# internal_env_board.net
KiCad netlist of a schematic drawn in EAGLE
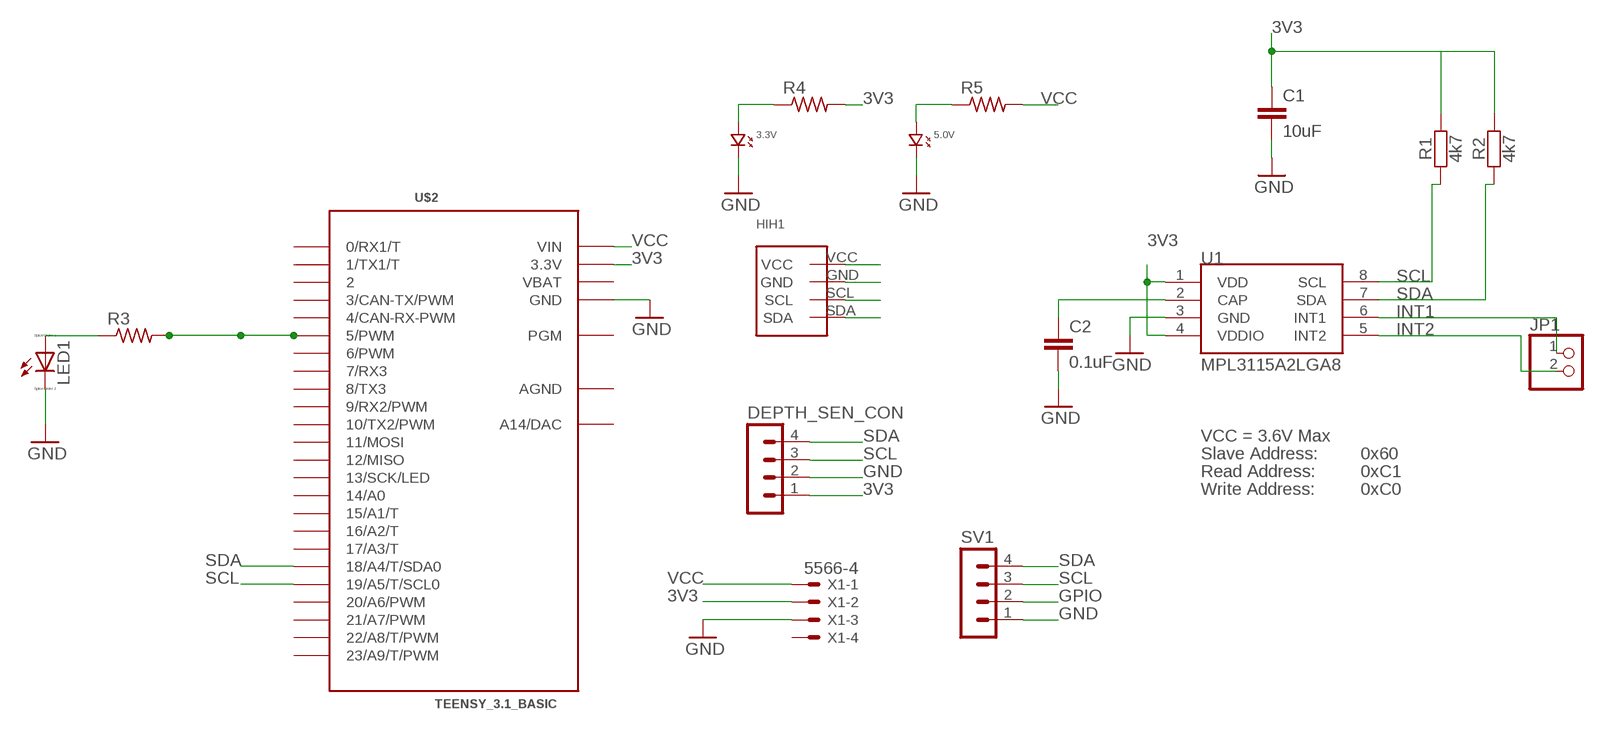
[diagram p0: schematic, sheet 1]

(export (version "E")
  (design (tool "Eeschema 10.0.6"))
  (components
    (comp (ref "3.3V")
      (value "LED.0805")
      (footprint "eagle-import:0805.LED")
      (libsource (lib "eagle-import") (part "LED.0805"))
    )
    (comp (ref "5.0V")
      (value "LED.0805")
      (footprint "eagle-import:0805.LED")
      (libsource (lib "eagle-import") (part "LED.0805"))
    )
    (comp (ref "C1")
      (value "10uF")
      (footprint "eagle-import:0805")
      (libsource (lib "eagle-import") (part "CAP0805"))
    )
    (comp (ref "C2")
      (value "0.1uF")
      (footprint "eagle-import:0805")
      (libsource (lib "eagle-import") (part "CAP0805"))
    )
    (comp (ref "DEPTH_SEN_CON")
      (value "MA04-1")
      (footprint "eagle-import:MA04-1")
      (libsource (lib "eagle-import") (part "MA04-1"))
    )
    (comp (ref "HIH1")
      (value "HIH7120")
      (footprint "eagle-import:SIP4")
      (libsource (lib "eagle-import") (part "HIH7120"))
    )
    (comp (ref "JP1")
      (value "PINHD-1X2")
      (footprint "eagle-import:1X02")
      (libsource (lib "eagle-import") (part "PINHD-1X2"))
    )
    (comp (ref "LED1")
      (value "LED_E")
      (footprint "eagle-import:LED_1206")
      (libsource (lib "eagle-import") (part "LED_E"))
    )
    (comp (ref "R1")
      (value "4k7")
      (footprint "eagle-import:R0805")
      (libsource (lib "eagle-import") (part "RESISTOR-R0805"))
    )
    (comp (ref "R2")
      (value "4k7")
      (footprint "eagle-import:R0805")
      (libsource (lib "eagle-import") (part "RESISTOR-R0805"))
    )
    (comp (ref "R3")
      (value "R-US_M1206")
      (footprint "eagle-import:M1206")
      (libsource (lib "eagle-import") (part "resistor_R-US_M1206"))
    )
    (comp (ref "R4")
      (value "R-US_R0805")
      (footprint "eagle-import:R0805")
      (libsource (lib "eagle-import") (part "R-US_R0805"))
    )
    (comp (ref "R5")
      (value "R-US_R0805")
      (footprint "eagle-import:R0805")
      (libsource (lib "eagle-import") (part "R-US_R0805"))
    )
    (comp (ref "SV1")
      (value "MA04-1")
      (footprint "eagle-import:MA04-1")
      (libsource (lib "eagle-import") (part "MA04-1"))
    )
    (comp (ref "U$2")
      (value "TEENSY_3.1_BASIC")
      (footprint "eagle-import:TEENSY_3.1_BASIC")
      (libsource (lib "eagle-import") (part "TEENSY_3.1_BASIC"))
    )
    (comp (ref "U1")
      (value "MPL3115A2LGA8")
      (footprint "eagle-import:LGA8")
      (libsource (lib "eagle-import") (part "MPL3115A2LGA8"))
    )
    (comp (ref "X1")
      (value "5566-4")
      (footprint "eagle-import:5566-4")
      (libsource (lib "eagle-import") (part "5566-4"))
    )
  )
  (nets
    (net (code "1") (name "/3V3") (class "Default")
      (node (ref "C1") (pin "1") (pinfunction "1_1") (pintype "passive"))
      (node (ref "DEPTH_SEN_CON") (pin "1") (pinfunction "1_1") (pintype "passive"))
      (node (ref "HIH1") (pin "VCC") (pinfunction "VCC_VCC") (pintype "power_in"))
      (node (ref "R1") (pin "2") (pinfunction "2_2") (pintype "passive"))
      (node (ref "R2") (pin "2") (pinfunction "2_2") (pintype "passive"))
      (node (ref "R4") (pin "2") (pinfunction "2_2") (pintype "passive"))
      (node (ref "U$2") (pin "3.3V") (pinfunction "3.3V_3.3V") (pintype "power_in"))
      (node (ref "U$2") (pin "3.3V1") (pinfunction "3.3V_3.3V1") (pintype "power_in"))
      (node (ref "U1") (pin "1") (pinfunction "VDD_1") (pintype "bidirectional"))
      (node (ref "U1") (pin "4") (pinfunction "VDDIO_4") (pintype "bidirectional"))
      (node (ref "X1") (pin "2") (pinfunction "S_2") (pintype "passive"))
    )
    (net (code "2") (name "/AGND") (class "Default")
      (node (ref "U$2") (pin "AGND") (pinfunction "AGND_AGND") (pintype "power_in"))
    )
    (net (code "3") (name "/GPIO") (class "Default")
      (node (ref "R3") (pin "2") (pinfunction "2_2") (pintype "passive"))
      (node (ref "SV1") (pin "2") (pinfunction "2_2") (pintype "passive"))
      (node (ref "U$2") (pin "5") (pinfunction "5/PWM_5") (pintype "bidirectional"))
    )
    (net (code "4") (name "/INT1") (class "Default")
      (node (ref "JP1") (pin "1") (pinfunction "1_1") (pintype "passive"))
      (node (ref "U1") (pin "6") (pinfunction "INT1_6") (pintype "bidirectional"))
    )
    (net (code "5") (name "/INT2") (class "Default")
      (node (ref "JP1") (pin "2") (pinfunction "2_2") (pintype "passive"))
      (node (ref "U1") (pin "5") (pinfunction "INT2_5") (pintype "bidirectional"))
    )
    (net (code "6") (name "/SCL") (class "Default")
      (node (ref "DEPTH_SEN_CON") (pin "3") (pinfunction "3_3") (pintype "passive"))
      (node (ref "HIH1") (pin "SCL") (pinfunction "SCL_SCL") (pintype "bidirectional"))
      (node (ref "R1") (pin "1") (pinfunction "1_1") (pintype "passive"))
      (node (ref "SV1") (pin "3") (pinfunction "3_3") (pintype "passive"))
      (node (ref "U$2") (pin "19/A5") (pinfunction "19/A5/T/SCL0_19/A5") (pintype "bidirectional"))
      (node (ref "U1") (pin "8") (pinfunction "SCL_8") (pintype "bidirectional"))
    )
    (net (code "7") (name "/SDA") (class "Default")
      (node (ref "DEPTH_SEN_CON") (pin "4") (pinfunction "4_4") (pintype "passive"))
      (node (ref "HIH1") (pin "SDA") (pinfunction "SDA_SDA") (pintype "bidirectional"))
      (node (ref "R2") (pin "1") (pinfunction "1_1") (pintype "passive"))
      (node (ref "SV1") (pin "4") (pinfunction "4_4") (pintype "passive"))
      (node (ref "U$2") (pin "18/A4") (pinfunction "18/A4/T/SDA0_18/A4") (pintype "bidirectional"))
      (node (ref "U1") (pin "7") (pinfunction "SDA_7") (pintype "bidirectional"))
    )
    (net (code "8") (name "/VBAT") (class "Default")
      (node (ref "U$2") (pin "VBAT") (pinfunction "VBAT_VBAT") (pintype "power_in"))
    )
    (net (code "9") (name "/VCC") (class "Default")
      (node (ref "R5") (pin "2") (pinfunction "2_2") (pintype "passive"))
      (node (ref "U$2") (pin "VIN") (pinfunction "VIN_VIN") (pintype "power_in"))
      (node (ref "X1") (pin "1") (pinfunction "S_1") (pintype "passive"))
    )
    (net (code "10") (name "GND") (class "Default")
      (node (ref "3.3V") (pin "P$2") (pinfunction "2_P$2") (pintype "bidirectional"))
      (node (ref "5.0V") (pin "P$2") (pinfunction "2_P$2") (pintype "bidirectional"))
      (node (ref "C1") (pin "2") (pinfunction "2_2") (pintype "passive"))
      (node (ref "C2") (pin "2") (pinfunction "2_2") (pintype "passive"))
      (node (ref "DEPTH_SEN_CON") (pin "2") (pinfunction "2_2") (pintype "passive"))
      (node (ref "HIH1") (pin "GND") (pinfunction "GND_GND") (pintype "power_in"))
      (node (ref "LED1") (pin "C") (pinfunction "C_C") (pintype "passive"))
      (node (ref "SV1") (pin "1") (pinfunction "1_1") (pintype "passive"))
      (node (ref "U$2") (pin "GND") (pinfunction "GND_GND") (pintype "power_in"))
      (node (ref "U$2") (pin "GND1") (pinfunction "GND_GND1") (pintype "power_in"))
      (node (ref "U1") (pin "3") (pinfunction "GND_3") (pintype "bidirectional"))
      (node (ref "X1") (pin "3") (pinfunction "S_3") (pintype "passive"))
    )
    (net (code "11") (name "Net-(3.3V-1)") (class "Default")
      (node (ref "3.3V") (pin "P$1") (pinfunction "1_P$1") (pintype "bidirectional"))
      (node (ref "R4") (pin "1") (pinfunction "1_1") (pintype "passive"))
    )
    (net (code "12") (name "Net-(5.0V-1)") (class "Default")
      (node (ref "5.0V") (pin "P$1") (pinfunction "1_P$1") (pintype "bidirectional"))
      (node (ref "R5") (pin "1") (pinfunction "1_1") (pintype "passive"))
    )
    (net (code "13") (name "Net-(LED1-PadA)") (class "Default")
      (node (ref "LED1") (pin "A") (pinfunction "A_A") (pintype "passive"))
      (node (ref "R3") (pin "1") (pinfunction "1_1") (pintype "passive"))
    )
    (net (code "14") (name "Net-(U1-CAP)") (class "Default")
      (node (ref "C2") (pin "1") (pinfunction "1_1") (pintype "passive"))
      (node (ref "U1") (pin "2") (pinfunction "CAP_2") (pintype "bidirectional"))
    )
    (net (code "15") (name "unconnected-(U$2-0{slash}RX1{slash}T-Pad0)") (class "Default")
      (node (ref "U$2") (pin "0") (pinfunction "0/RX1/T_0") (pintype "bidirectional"))
    )
    (net (code "16") (name "unconnected-(U$2-1{slash}TX1{slash}T-Pad1)") (class "Default")
      (node (ref "U$2") (pin "1") (pinfunction "1/TX1/T_1") (pintype "bidirectional"))
    )
    (net (code "17") (name "unconnected-(U$2-3{slash}CAN-TX{slash}PWM-Pad3)") (class "Default")
      (node (ref "U$2") (pin "3") (pinfunction "3/CAN-TX/PWM_3") (pintype "bidirectional"))
    )
    (net (code "18") (name "unconnected-(U$2-4{slash}CAN-RX-PWM-Pad4)") (class "Default")
      (node (ref "U$2") (pin "4") (pinfunction "4/CAN-RX-PWM_4") (pintype "bidirectional"))
    )
    (net (code "19") (name "unconnected-(U$2-6{slash}PWM-Pad6)") (class "Default")
      (node (ref "U$2") (pin "6") (pinfunction "6/PWM_6") (pintype "bidirectional"))
    )
    (net (code "20") (name "unconnected-(U$2-7{slash}RX3-Pad7)") (class "Default")
      (node (ref "U$2") (pin "7") (pinfunction "7/RX3_7") (pintype "bidirectional"))
    )
    (net (code "21") (name "unconnected-(U$2-8{slash}TX3-Pad8)") (class "Default")
      (node (ref "U$2") (pin "8") (pinfunction "8/TX3_8") (pintype "bidirectional"))
    )
    (net (code "22") (name "unconnected-(U$2-9{slash}RX2{slash}PWM-Pad9)") (class "Default")
      (node (ref "U$2") (pin "9") (pinfunction "9/RX2/PWM_9") (pintype "bidirectional"))
    )
    (net (code "23") (name "unconnected-(U$2-10{slash}TX2{slash}PWM-Pad10)") (class "Default")
      (node (ref "U$2") (pin "10") (pinfunction "10/TX2/PWM_10") (pintype "bidirectional"))
    )
    (net (code "24") (name "unconnected-(U$2-11{slash}MOSI-Pad11)") (class "Default")
      (node (ref "U$2") (pin "11") (pinfunction "11/MOSI_11") (pintype "bidirectional"))
    )
    (net (code "25") (name "unconnected-(U$2-12{slash}MISO-Pad12)") (class "Default")
      (node (ref "U$2") (pin "12") (pinfunction "12/MISO_12") (pintype "bidirectional"))
    )
    (net (code "26") (name "unconnected-(U$2-13{slash}SCK{slash}LED-Pad13)") (class "Default")
      (node (ref "U$2") (pin "13") (pinfunction "13/SCK/LED_13") (pintype "bidirectional"))
    )
    (net (code "27") (name "unconnected-(U$2-15{slash}A1{slash}T-Pad15{slash}A1)") (class "Default")
      (node (ref "U$2") (pin "15/A1") (pinfunction "15/A1/T_15/A1") (pintype "bidirectional"))
    )
    (net (code "28") (name "unconnected-(U$2-16{slash}A2{slash}T-Pad16{slash}A2)") (class "Default")
      (node (ref "U$2") (pin "16/A2") (pinfunction "16/A2/T_16/A2") (pintype "bidirectional"))
    )
    (net (code "29") (name "unconnected-(U$2-17{slash}A3{slash}T-Pad17{slash}A3)") (class "Default")
      (node (ref "U$2") (pin "17/A3") (pinfunction "17/A3/T_17/A3") (pintype "bidirectional"))
    )
    (net (code "30") (name "unconnected-(U$2-20{slash}A6{slash}PWM-Pad20{slash}A6)") (class "Default")
      (node (ref "U$2") (pin "20/A6") (pinfunction "20/A6/PWM_20/A6") (pintype "bidirectional"))
    )
    (net (code "31") (name "unconnected-(U$2-21{slash}A7{slash}PWM-Pad21{slash}A7)") (class "Default")
      (node (ref "U$2") (pin "21/A7") (pinfunction "21/A7/PWM_21/A7") (pintype "bidirectional"))
    )
    (net (code "32") (name "unconnected-(U$2-22{slash}A8{slash}T{slash}PWM-Pad22{slash}A8)") (class "Default")
      (node (ref "U$2") (pin "22/A8") (pinfunction "22/A8/T/PWM_22/A8") (pintype "bidirectional"))
    )
    (net (code "33") (name "unconnected-(U$2-23{slash}A9{slash}T{slash}PWM-Pad23{slash}A9)") (class "Default")
      (node (ref "U$2") (pin "23/A9") (pinfunction "23/A9/T/PWM_23/A9") (pintype "bidirectional"))
    )
    (net (code "34") (name "unconnected-(U$2-A14{slash}DAC-PadA14)") (class "Default")
      (node (ref "U$2") (pin "A14") (pinfunction "A14/DAC_A14") (pintype "bidirectional"))
    )
    (net (code "35") (name "unconnected-(U$2-Pad2)") (class "Default")
      (node (ref "U$2") (pin "2") (pinfunction "2_2") (pintype "bidirectional"))
    )
    (net (code "36") (name "unconnected-(U$2-Pad14{slash}A0)") (class "Default")
      (node (ref "U$2") (pin "14/A0") (pinfunction "14/A0_14/A0") (pintype "bidirectional"))
    )
    (net (code "37") (name "unconnected-(U$2-PadPGM)") (class "Default")
      (node (ref "U$2") (pin "PGM") (pinfunction "PGM_PGM") (pintype "bidirectional"))
    )
    (net (code "38") (name "unconnected-(X1D-S-Pad4)") (class "Default")
      (node (ref "X1") (pin "4") (pinfunction "S_4") (pintype "passive"))
    )
  )
)
